# X-Fly.net
KiCad netlist of a schematic drawn in Altium Designer
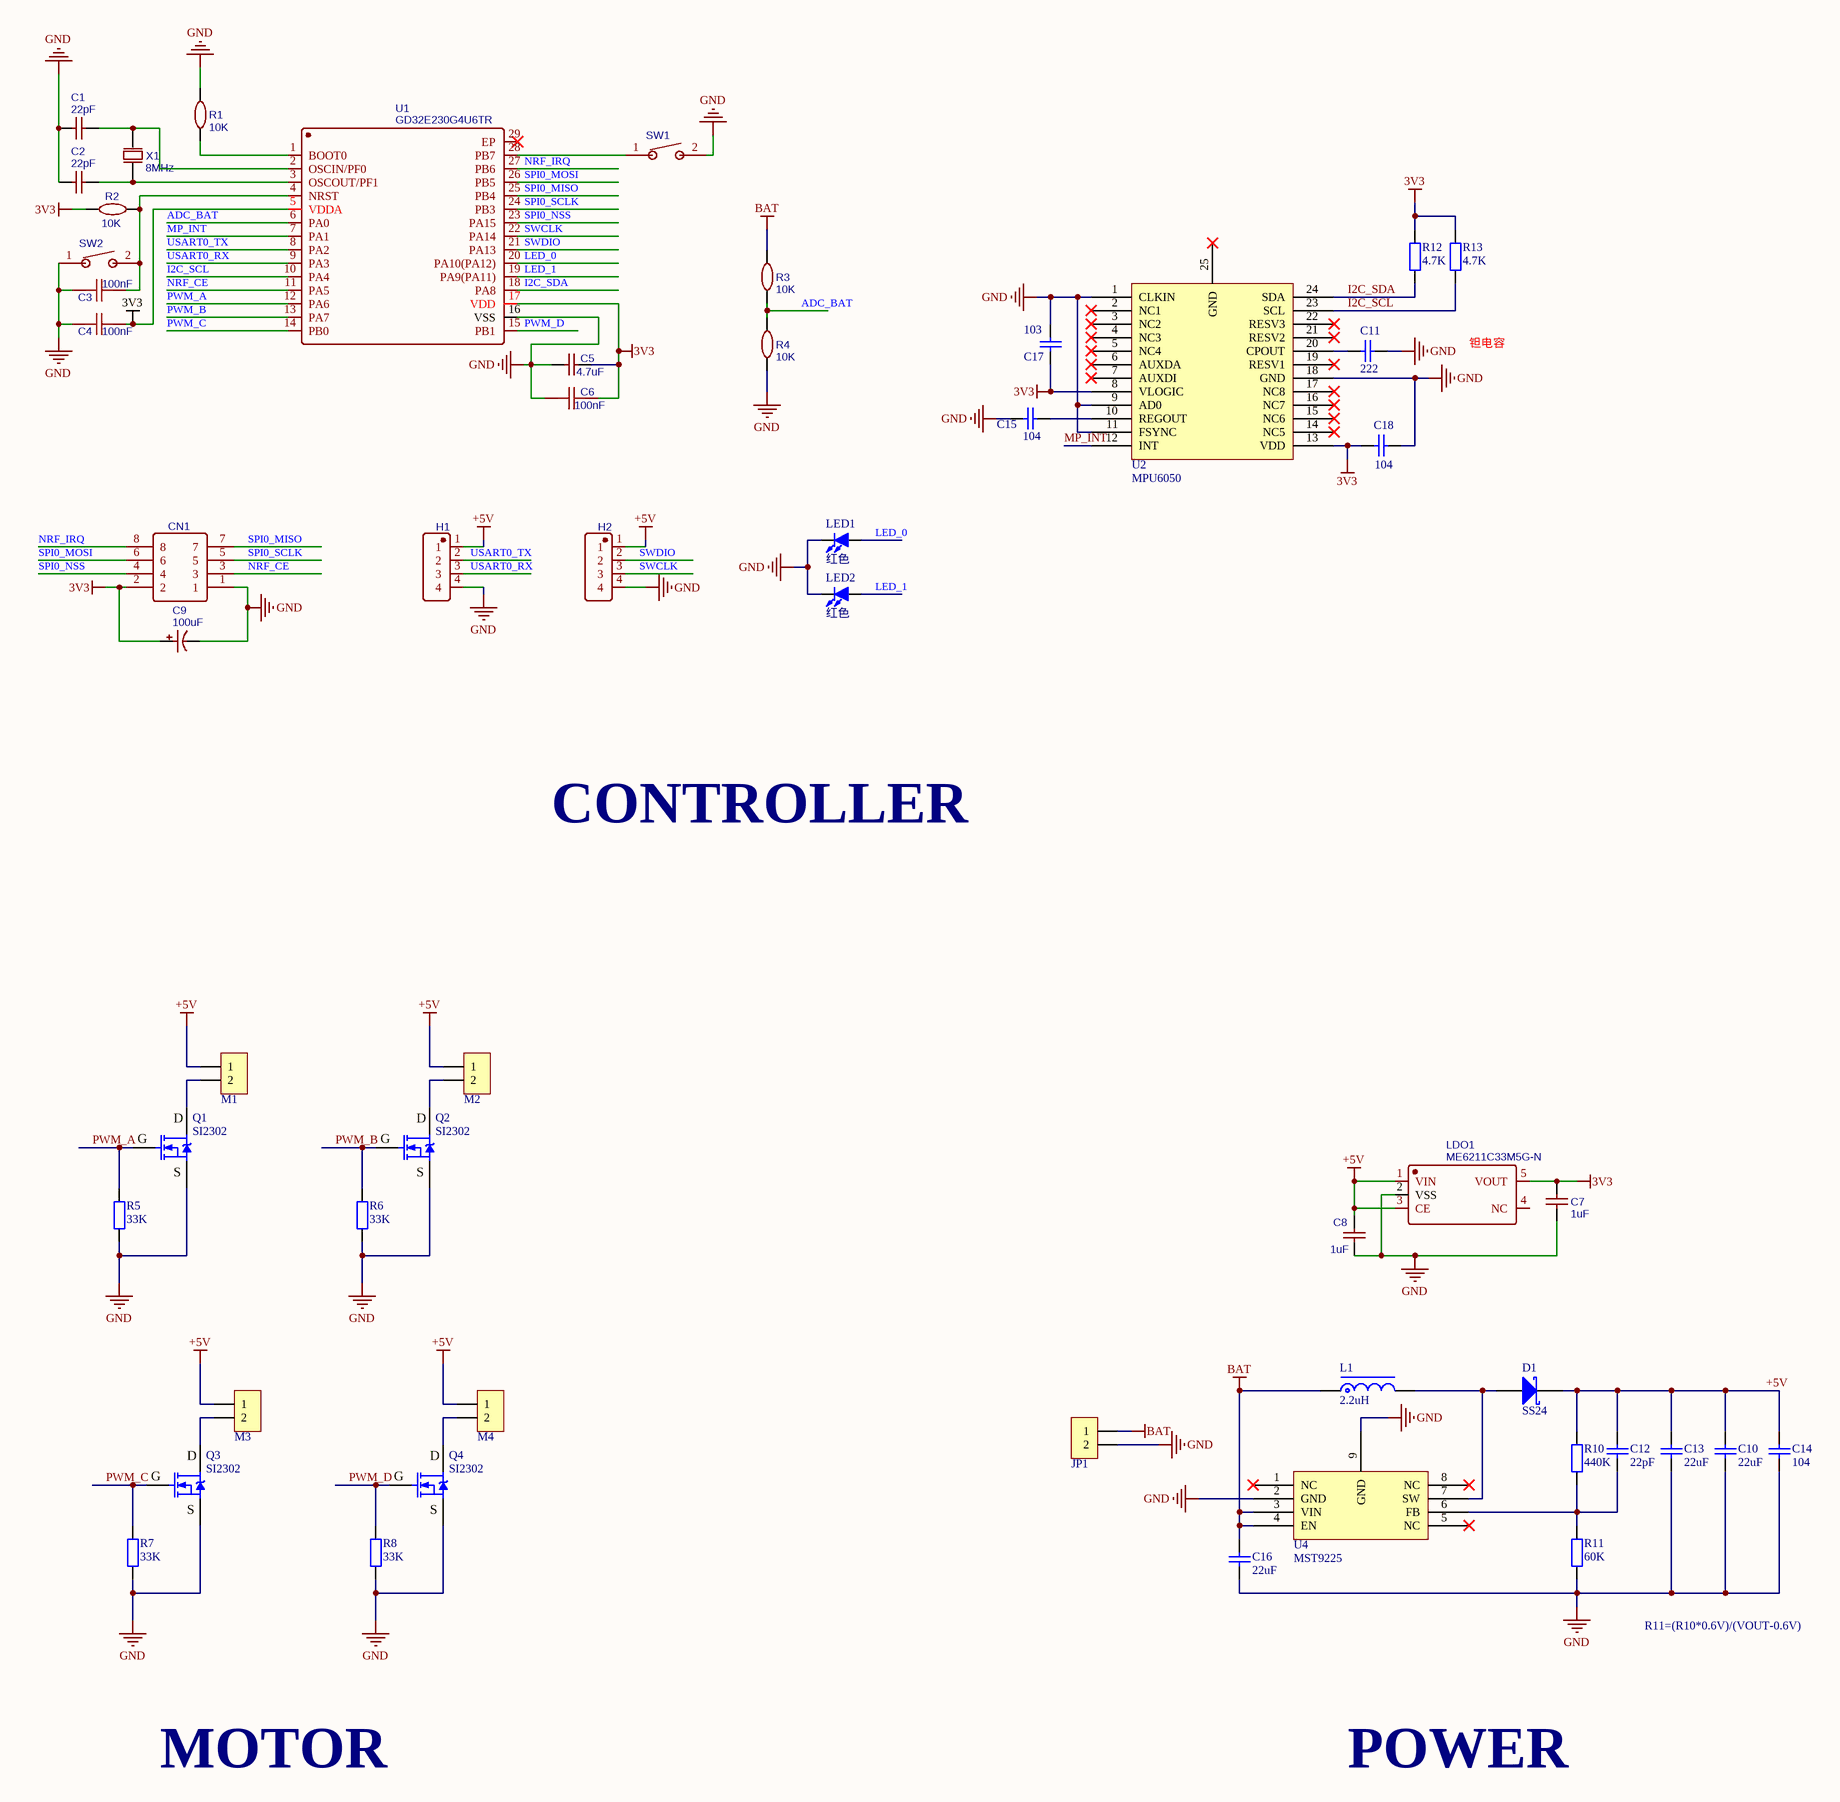
[diagram p0: X-Fly.SchDoc]

(export (version "E")
  (design (tool "Eeschema 10.0.6"))
  (components
    (comp (ref "C1")
      (value "22pF")
      (footprint "C0603_L")
      (fields
        (field (name "BOM_MANUFACTURER PART") "CC0603JRNPO9BN220")
        (field (name "BOM_SUPPLIER PART") "C105620")
      )
      (libsource (lib "altium-import") (part "root_0_22pF_"))
    )
    (comp (ref "C2")
      (value "22pF")
      (footprint "C0603_L")
      (fields
        (field (name "BOM_MANUFACTURER PART") "CC0603JRNPO9BN220")
        (field (name "BOM_SUPPLIER PART") "C105620")
      )
      (libsource (lib "altium-import") (part "root_0_22pF_"))
    )
    (comp (ref "C3")
      (value "100nF")
      (footprint "C0603_L")
      (fields
        (field (name "BOM_MANUFACTURER PART") "CC0603KRX7R9BB104")
        (field (name "BOM_SUPPLIER PART") "C14663")
      )
      (libsource (lib "altium-import") (part "root_2_100nF_"))
    )
    (comp (ref "C4")
      (value "100nF")
      (footprint "C0603_L")
      (fields
        (field (name "BOM_MANUFACTURER PART") "CC0603KRX7R9BB104")
        (field (name "BOM_SUPPLIER PART") "C14663")
      )
      (libsource (lib "altium-import") (part "root_0_100nF_"))
    )
    (comp (ref "C5")
      (value "4.7uF")
      (footprint "C0603_L")
      (fields
        (field (name "BOM_MANUFACTURER PART") "CL10A475KO8NNNC")
        (field (name "BOM_SUPPLIER PART") "C19666")
      )
      (libsource (lib "altium-import") (part "root_2_4.7uF_"))
    )
    (comp (ref "C6")
      (value "100nF")
      (footprint "C0603_L")
      (fields
        (field (name "BOM_MANUFACTURER PART") "CC0603KRX7R9BB104")
        (field (name "BOM_SUPPLIER PART") "C14663")
      )
      (libsource (lib "altium-import") (part "root_0_100nF_"))
    )
    (comp (ref "C7")
      (value "1uF")
      (footprint "C0603_L")
      (fields
        (field (name "BOM_MANUFACTURER PART") "CL10A105KB8NNNC")
        (field (name "BOM_SUPPLIER PART") "C15849")
      )
      (libsource (lib "altium-import") (part "root_1_1uF_"))
    )
    (comp (ref "C8")
      (value "1uF")
      (footprint "C0603_L")
      (fields
        (field (name "BOM_MANUFACTURER PART") "CL10A105KB8NNNC")
        (field (name "BOM_SUPPLIER PART") "C15849")
      )
      (libsource (lib "altium-import") (part "root_1_1uF_"))
    )
    (comp (ref "C9")
      (value "100uF")
      (footprint "CAP 2.5*6.3*11.2-H - BK")
      (fields
        (field (name "BOM_MANUFACTURER PART") "35YXJ100M6.3X11")
        (field (name "BOM_SUPPLIER PART") "C88754")
      )
      (libsource (lib "altium-import") (part "root_0_100uF_"))
    )
    (comp (ref "C10")
      (value "22uF")
      (footprint "C0603_L")
      (description "贴片电容")
      (libsource (lib "0.1 - 电阻-电容-电感-磁珠-电位器") (part "C"))
    )
    (comp (ref "C11")
      (value "222")
      (footprint "C_3216")
      (description "贴片电容")
      (libsource (lib "0.1 - 电阻-电容-电感-磁珠-电位器") (part "C"))
    )
    (comp (ref "C12")
      (value "22pF")
      (footprint "C0603_L")
      (description "贴片电容")
      (libsource (lib "0.1 - 电阻-电容-电感-磁珠-电位器") (part "C"))
    )
    (comp (ref "C13")
      (value "22uF")
      (footprint "C0603_L")
      (description "贴片电容")
      (libsource (lib "0.1 - 电阻-电容-电感-磁珠-电位器") (part "C"))
    )
    (comp (ref "C14")
      (value "104")
      (footprint "C0603_L")
      (description "贴片电容")
      (libsource (lib "0.1 - 电阻-电容-电感-磁珠-电位器") (part "C"))
    )
    (comp (ref "C15")
      (value "104")
      (footprint "C0603_L")
      (description "贴片电容")
      (libsource (lib "0.1 - 电阻-电容-电感-磁珠-电位器") (part "C"))
    )
    (comp (ref "C16")
      (value "22uF")
      (footprint "C0603_L")
      (description "贴片电容")
      (libsource (lib "0.1 - 电阻-电容-电感-磁珠-电位器") (part "C"))
    )
    (comp (ref "C17")
      (value "103")
      (footprint "C0603_L")
      (description "贴片电容")
      (libsource (lib "0.1 - 电阻-电容-电感-磁珠-电位器") (part "C"))
    )
    (comp (ref "C18")
      (value "104")
      (footprint "C0603_L")
      (description "贴片电容")
      (libsource (lib "0.1 - 电阻-电容-电感-磁珠-电位器") (part "C"))
    )
    (comp (ref "CN1")
      (value "A2005WV-2X4P")
      (footprint ".4G无线模块")
      (fields
        (field (name "BOM_SUPPLIER PART") "C225289")
        (field (name "BOM_MANUFACTURER PART") "A2005WV-2x4P")
        (field (name "CONTRIBUTOR") "LCSC")
      )
      (libsource (lib "altium-import") (part "root_1_A2005WV-2X4P_"))
    )
    (comp (ref "D1")
      (value "SS24")
      (footprint "SMB")
      (description "肖特基二极管")
      (libsource (lib "0.2 - 二极管-TVS-ESD-整流桥") (part "SS24"))
    )
    (comp (ref "H1")
      (value "1125-1104G0S116C001")
      (footprint "HDR2.54-WI-4P")
      (fields (field (name "BOM_SUPPLIER PART") "C920779") (field (name "CONTRIBUTOR") "LCSC"))
      (libsource (lib "altium-import") (part "root_0_1125-1104G0S116C001_"))
    )
    (comp (ref "H2")
      (value "1125-1104G0S116C001")
      (footprint "HDR2.54-WI-4P")
      (fields (field (name "BOM_SUPPLIER PART") "C920779") (field (name "CONTRIBUTOR") "LCSC"))
      (libsource (lib "altium-import") (part "root_0_1125-1104G0S116C001_"))
    )
    (comp (ref "JP1")
      (value "HDR-1X2")
      (footprint "XH2.54-WI-2P")
      (description "2P接插件")
      (libsource (lib "") (part "Header 2_1"))
    )
    (comp (ref "L1")
      (value "2.2uH")
      (footprint "CD52")
      (description "太诱-NR磁胶电感")
      (libsource (lib "0.1 - 电阻-电容-电感-磁珠-电位器") (part "L-NR"))
    )
    (comp (ref "LDO1")
      (value "ME6211C33M5G-N")
      (footprint "SOT-23-5")
      (fields (field (name "BOM_SUPPLIER PART") "C82942"))
      (libsource (lib "altium-import") (part "root_0_ME6211C33M5G-N_"))
    )
    (comp (ref "LED1")
      (value "红色")
      (footprint "LED0603_R")
      (description "贴片LED")
      (libsource (lib "0.3 - LED发光二极管") (part "LED-SMD"))
    )
    (comp (ref "LED2")
      (value "红色")
      (footprint "LED0603_R")
      (description "贴片LED")
      (libsource (lib "0.3 - LED发光二极管") (part "LED-SMD"))
    )
    (comp (ref "M1")
      (value "HDR-1X2")
      (footprint "XH2.54-WI-2P")
      (description "2P接插件")
      (libsource (lib "5.5 - 接插件-脚距2.54 (100mil) ") (part "Header 2"))
    )
    (comp (ref "M2")
      (value "HDR-1X2")
      (footprint "XH2.54-WI-2P")
      (description "2P接插件")
      (libsource (lib "5.5 - 接插件-脚距2.54 (100mil) ") (part "Header 2"))
    )
    (comp (ref "M3")
      (value "HDR-1X2")
      (footprint "XH2.54-WI-2P")
      (description "2P接插件")
      (libsource (lib "5.5 - 接插件-脚距2.54 (100mil) ") (part "Header 2"))
    )
    (comp (ref "M4")
      (value "HDR-1X2")
      (footprint "XH2.54-WI-2P")
      (description "2P接插件")
      (libsource (lib "5.5 - 接插件-脚距2.54 (100mil) ") (part "Header 2"))
    )
    (comp (ref "Q1")
      (value "SI2302")
      (footprint "SOT23-3N")
      (description "N沟道 20V/3A")
      (libsource (lib "0.4 - 三极管-场效应管-可控硅") (part "SI2302"))
    )
    (comp (ref "Q2")
      (value "SI2302")
      (footprint "SOT23-3N")
      (description "N沟道 20V/3A")
      (libsource (lib "0.4 - 三极管-场效应管-可控硅") (part "SI2302"))
    )
    (comp (ref "Q3")
      (value "SI2302")
      (footprint "SOT23-3N")
      (description "N沟道 20V/3A")
      (libsource (lib "0.4 - 三极管-场效应管-可控硅") (part "SI2302"))
    )
    (comp (ref "Q4")
      (value "SI2302")
      (footprint "SOT23-3N")
      (description "N沟道 20V/3A")
      (libsource (lib "0.4 - 三极管-场效应管-可控硅") (part "SI2302"))
    )
    (comp (ref "R1")
      (value "10K")
      (footprint "R0603_L")
      (fields
        (field (name "BOM_MANUFACTURER PART") "RC0603FR-0710KL")
        (field (name "BOM_SUPPLIER PART") "C98220")
      )
      (libsource (lib "altium-import") (part "root_1_10K_"))
    )
    (comp (ref "R2")
      (value "10K")
      (footprint "R0603_L")
      (fields
        (field (name "BOM_MANUFACTURER PART") "RC0603FR-0710KL")
        (field (name "BOM_SUPPLIER PART") "C98220")
      )
      (libsource (lib "altium-import") (part "root_2_10K_"))
    )
    (comp (ref "R3")
      (value "10K")
      (footprint "R0603_L")
      (fields
        (field (name "BOM_MANUFACTURER PART") "RC0603FR-0710KL")
        (field (name "BOM_SUPPLIER PART") "C98220")
      )
      (libsource (lib "altium-import") (part "root_3_10K_"))
    )
    (comp (ref "R4")
      (value "10K")
      (footprint "R0603_L")
      (fields
        (field (name "BOM_MANUFACTURER PART") "RC0603FR-0710KL")
        (field (name "BOM_SUPPLIER PART") "C98220")
      )
      (libsource (lib "altium-import") (part "root_3_10K_"))
    )
    (comp (ref "R5")
      (value "33K")
      (footprint "R0603_L")
      (description "贴片电阻")
      (libsource (lib "0.1 - 电阻-电容-电感-磁珠-电位器") (part "R"))
    )
    (comp (ref "R6")
      (value "33K")
      (footprint "R0603_L")
      (description "贴片电阻")
      (libsource (lib "0.1 - 电阻-电容-电感-磁珠-电位器") (part "R"))
    )
    (comp (ref "R7")
      (value "33K")
      (footprint "R0603_L")
      (description "贴片电阻")
      (libsource (lib "0.1 - 电阻-电容-电感-磁珠-电位器") (part "R"))
    )
    (comp (ref "R8")
      (value "33K")
      (footprint "R0603_L")
      (description "贴片电阻")
      (libsource (lib "0.1 - 电阻-电容-电感-磁珠-电位器") (part "R"))
    )
    (comp (ref "R10")
      (value "440K")
      (footprint "R0603_L")
      (description "贴片电阻")
      (libsource (lib "0.1 - 电阻-电容-电感-磁珠-电位器") (part "R"))
    )
    (comp (ref "R11")
      (value "60K")
      (footprint "R0603_L")
      (description "贴片电阻")
      (libsource (lib "0.1 - 电阻-电容-电感-磁珠-电位器") (part "R"))
    )
    (comp (ref "R12")
      (value "4.7K")
      (footprint "R0603_L")
      (description "贴片电阻")
      (libsource (lib "0.1 - 电阻-电容-电感-磁珠-电位器") (part "R"))
    )
    (comp (ref "R13")
      (value "4.7K")
      (footprint "R0603_L")
      (description "贴片电阻")
      (libsource (lib "0.1 - 电阻-电容-电感-磁珠-电位器") (part "R"))
    )
    (comp (ref "SW1")
      (value "TSA363G25-250B")
      (footprint "SW SMD-3*6*5")
      (fields (field (name "BOM_SUPPLIER PART") "C354943") (field (name "CONTRIBUTOR") "LCSC"))
      (libsource (lib "altium-import") (part "root_0_TSA363G25-250B_"))
    )
    (comp (ref "SW2")
      (value "TSA363G25-250B")
      (footprint "SW SMD-3*6*5")
      (fields (field (name "BOM_SUPPLIER PART") "C354943") (field (name "CONTRIBUTOR") "LCSC"))
      (libsource (lib "altium-import") (part "root_0_TSA363G25-250B_"))
    )
    (comp (ref "U1")
      (value "GD32E230G4U6TR")
      (footprint "QFN28 5x5_M")
      (fields (field (name "BOM_SUPPLIER PART") "C380784") (field (name "CONTRIBUTOR") "LCSC"))
      (libsource (lib "altium-import") (part "root_0_GD32E230G4U6TR_"))
    )
    (comp (ref "U2")
      (value "MPU6050")
      (footprint "QFN24 4x4_N")
      (libsource (lib "Aircraft Controller") (part "MPU6050"))
    )
    (comp (ref "U4")
      (value "MST9225")
      (footprint "ESOP8_N")
      (description "单节锂电池2A升压芯片")
      (libsource (lib "Aircraft Controller") (part "MST9225"))
    )
    (comp (ref "X1")
      (value "8MHz")
      (footprint "OSC 5032-2P")
      (fields (field (name "BOM_SUPPLIER PART") "C122522") (field (name "CONTRIBUTOR") "LCSC"))
      (libsource (lib "altium-import") (part "root_1_8MHz_"))
    )
  )
  (nets
    (net (code "1") (name "+5V") (class "Default")
      (node (ref "C10") (pin "2") (pinfunction "2_2") (pintype "passive"))
      (node (ref "C12") (pin "2") (pinfunction "2_2") (pintype "passive"))
      (node (ref "C13") (pin "2") (pinfunction "2_2") (pintype "passive"))
      (node (ref "C14") (pin "2") (pinfunction "2_2") (pintype "passive"))
      (node (ref "C8") (pin "2") (pinfunction "2_2") (pintype "passive"))
      (node (ref "D1") (pin "2") (pinfunction "K_2") (pintype "passive"))
      (node (ref "H1") (pin "1") (pinfunction "1_1") (pintype "passive"))
      (node (ref "H2") (pin "1") (pinfunction "1_1") (pintype "passive"))
      (node (ref "LDO1") (pin "1") (pinfunction "VIN_1") (pintype "passive"))
      (node (ref "LDO1") (pin "3") (pinfunction "CE_3") (pintype "passive"))
      (node (ref "M1") (pin "1") (pinfunction "1_1") (pintype "passive"))
      (node (ref "M2") (pin "1") (pinfunction "1_1") (pintype "passive"))
      (node (ref "M3") (pin "1") (pinfunction "1_1") (pintype "passive"))
      (node (ref "M4") (pin "1") (pinfunction "1_1") (pintype "passive"))
      (node (ref "R10") (pin "2") (pinfunction "2_2") (pintype "passive"))
    )
    (net (code "2") (name "/ADC_BAT") (class "Default")
      (node (ref "R3") (pin "2") (pinfunction "2_2") (pintype "passive"))
      (node (ref "R4") (pin "1") (pinfunction "1_1") (pintype "passive"))
      (node (ref "U1") (pin "6") (pinfunction "PA0_6") (pintype "passive"))
    )
    (net (code "3") (name "/I2C_SCL") (class "Default")
      (node (ref "R13") (pin "1") (pinfunction "1_1") (pintype "passive"))
      (node (ref "U1") (pin "10") (pinfunction "PA4_10") (pintype "passive"))
      (node (ref "U2") (pin "23") (pinfunction "SCL_23") (pintype "passive"))
    )
    (net (code "4") (name "/I2C_SDA") (class "Default")
      (node (ref "R12") (pin "1") (pinfunction "1_1") (pintype "passive"))
      (node (ref "U1") (pin "18") (pinfunction "PA8_18") (pintype "passive"))
      (node (ref "U2") (pin "24") (pinfunction "SDA_24") (pintype "passive"))
    )
    (net (code "5") (name "/LED_0") (class "Default")
      (node (ref "LED1") (pin "1") (pinfunction "A_1") (pintype "passive"))
      (node (ref "U1") (pin "20") (pinfunction "PA10(PA12)_20") (pintype "passive"))
    )
    (net (code "6") (name "/LED_1") (class "Default")
      (node (ref "LED2") (pin "1") (pinfunction "A_1") (pintype "passive"))
      (node (ref "U1") (pin "19") (pinfunction "PA9(PA11)_19") (pintype "passive"))
    )
    (net (code "7") (name "/MP_INT") (class "Default")
      (node (ref "U1") (pin "7") (pinfunction "PA1_7") (pintype "passive"))
      (node (ref "U2") (pin "12") (pinfunction "INT_12") (pintype "passive"))
    )
    (net (code "8") (name "/NRF_CE") (class "Default")
      (node (ref "CN1") (pin "3") (pinfunction "3_3") (pintype "passive"))
      (node (ref "U1") (pin "11") (pinfunction "PA5_11") (pintype "passive"))
    )
    (net (code "9") (name "/NRF_IRQ") (class "Default")
      (node (ref "CN1") (pin "8") (pinfunction "8_8") (pintype "passive"))
      (node (ref "U1") (pin "27") (pinfunction "PB6_27") (pintype "passive"))
    )
    (net (code "10") (name "/PWM_A") (class "Default")
      (node (ref "Q1") (pin "1") (pinfunction "G_1") (pintype "passive"))
      (node (ref "R5") (pin "2") (pinfunction "2_2") (pintype "passive"))
      (node (ref "U1") (pin "12") (pinfunction "PA6_12") (pintype "passive"))
    )
    (net (code "11") (name "/PWM_B") (class "Default")
      (node (ref "Q2") (pin "1") (pinfunction "G_1") (pintype "passive"))
      (node (ref "R6") (pin "2") (pinfunction "2_2") (pintype "passive"))
      (node (ref "U1") (pin "13") (pinfunction "PA7_13") (pintype "passive"))
    )
    (net (code "12") (name "/PWM_C") (class "Default")
      (node (ref "Q3") (pin "1") (pinfunction "G_1") (pintype "passive"))
      (node (ref "R7") (pin "2") (pinfunction "2_2") (pintype "passive"))
      (node (ref "U1") (pin "14") (pinfunction "PB0_14") (pintype "passive"))
    )
    (net (code "13") (name "/PWM_D") (class "Default")
      (node (ref "Q4") (pin "1") (pinfunction "G_1") (pintype "passive"))
      (node (ref "R8") (pin "2") (pinfunction "2_2") (pintype "passive"))
      (node (ref "U1") (pin "15") (pinfunction "PB1_15") (pintype "passive"))
    )
    (net (code "14") (name "/SPI0_MISO") (class "Default")
      (node (ref "CN1") (pin "7") (pinfunction "7_7") (pintype "passive"))
      (node (ref "U1") (pin "25") (pinfunction "PB4_25") (pintype "passive"))
    )
    (net (code "15") (name "/SPI0_MOSI") (class "Default")
      (node (ref "CN1") (pin "6") (pinfunction "6_6") (pintype "passive"))
      (node (ref "U1") (pin "26") (pinfunction "PB5_26") (pintype "passive"))
    )
    (net (code "16") (name "/SPI0_NSS") (class "Default")
      (node (ref "CN1") (pin "4") (pinfunction "4_4") (pintype "passive"))
      (node (ref "U1") (pin "23") (pinfunction "PA15_23") (pintype "passive"))
    )
    (net (code "17") (name "/SPI0_SCLK") (class "Default")
      (node (ref "CN1") (pin "5") (pinfunction "5_5") (pintype "passive"))
      (node (ref "U1") (pin "24") (pinfunction "PB3_24") (pintype "passive"))
    )
    (net (code "18") (name "/SWCLK") (class "Default")
      (node (ref "H2") (pin "3") (pinfunction "3_3") (pintype "passive"))
      (node (ref "U1") (pin "22") (pinfunction "PA14_22") (pintype "passive"))
    )
    (net (code "19") (name "/SWDIO") (class "Default")
      (node (ref "H2") (pin "2") (pinfunction "2_2") (pintype "passive"))
      (node (ref "U1") (pin "21") (pinfunction "PA13_21") (pintype "passive"))
    )
    (net (code "20") (name "/USART0_RX") (class "Default")
      (node (ref "H1") (pin "3") (pinfunction "3_3") (pintype "passive"))
      (node (ref "U1") (pin "9") (pinfunction "PA3_9") (pintype "passive"))
    )
    (net (code "21") (name "/USART0_TX") (class "Default")
      (node (ref "H1") (pin "2") (pinfunction "2_2") (pintype "passive"))
      (node (ref "U1") (pin "8") (pinfunction "PA2_8") (pintype "passive"))
    )
    (net (code "22") (name "3V3") (class "Default")
      (node (ref "C17") (pin "1") (pinfunction "1_1") (pintype "passive"))
      (node (ref "C18") (pin "1") (pinfunction "1_1") (pintype "passive"))
      (node (ref "C4") (pin "2") (pinfunction "2_2") (pintype "passive"))
      (node (ref "C5") (pin "1") (pinfunction "1_1") (pintype "passive"))
      (node (ref "C6") (pin "2") (pinfunction "2_2") (pintype "passive"))
      (node (ref "C7") (pin "2") (pinfunction "2_2") (pintype "passive"))
      (node (ref "C9") (pin "1") (pinfunction "1_1") (pintype "passive"))
      (node (ref "CN1") (pin "2") (pinfunction "2_2") (pintype "passive"))
      (node (ref "LDO1") (pin "5") (pinfunction "VOUT_5") (pintype "passive"))
      (node (ref "R12") (pin "2") (pinfunction "2_2") (pintype "passive"))
      (node (ref "R13") (pin "2") (pinfunction "2_2") (pintype "passive"))
      (node (ref "R2") (pin "2") (pinfunction "2_2") (pintype "passive"))
      (node (ref "U1") (pin "17") (pinfunction "VDD_17") (pintype "passive"))
      (node (ref "U1") (pin "5") (pinfunction "VDDA_5") (pintype "passive"))
      (node (ref "U2") (pin "13") (pinfunction "VDD_13") (pintype "passive"))
      (node (ref "U2") (pin "8") (pinfunction "VLOGIC_8") (pintype "passive"))
    )
    (net (code "23") (name "BAT") (class "Default")
      (node (ref "C16") (pin "2") (pinfunction "2_2") (pintype "passive"))
      (node (ref "JP1") (pin "1") (pinfunction "1_1") (pintype "passive"))
      (node (ref "L1") (pin "1") (pinfunction "1_1") (pintype "passive"))
      (node (ref "R3") (pin "1") (pinfunction "1_1") (pintype "passive"))
      (node (ref "U4") (pin "3") (pinfunction "VIN_3") (pintype "passive"))
      (node (ref "U4") (pin "4") (pinfunction "EN_4") (pintype "passive"))
    )
    (net (code "24") (name "GND") (class "Default")
      (node (ref "C1") (pin "1") (pinfunction "1_1") (pintype "passive"))
      (node (ref "C10") (pin "1") (pinfunction "1_1") (pintype "passive"))
      (node (ref "C11") (pin "1") (pinfunction "1_1") (pintype "passive"))
      (node (ref "C13") (pin "1") (pinfunction "1_1") (pintype "passive"))
      (node (ref "C14") (pin "1") (pinfunction "1_1") (pintype "passive"))
      (node (ref "C15") (pin "2") (pinfunction "2_2") (pintype "passive"))
      (node (ref "C16") (pin "1") (pinfunction "1_1") (pintype "passive"))
      (node (ref "C17") (pin "2") (pinfunction "2_2") (pintype "passive"))
      (node (ref "C18") (pin "2") (pinfunction "2_2") (pintype "passive"))
      (node (ref "C2") (pin "1") (pinfunction "1_1") (pintype "passive"))
      (node (ref "C3") (pin "2") (pinfunction "2_2") (pintype "passive"))
      (node (ref "C4") (pin "1") (pinfunction "1_1") (pintype "passive"))
      (node (ref "C5") (pin "2") (pinfunction "2_2") (pintype "passive"))
      (node (ref "C6") (pin "1") (pinfunction "1_1") (pintype "passive"))
      (node (ref "C7") (pin "1") (pinfunction "1_1") (pintype "passive"))
      (node (ref "C8") (pin "1") (pinfunction "1_1") (pintype "passive"))
      (node (ref "C9") (pin "2") (pinfunction "2_2") (pintype "passive"))
      (node (ref "CN1") (pin "1") (pinfunction "1_1") (pintype "passive"))
      (node (ref "H1") (pin "4") (pinfunction "4_4") (pintype "passive"))
      (node (ref "H2") (pin "4") (pinfunction "4_4") (pintype "passive"))
      (node (ref "JP1") (pin "2") (pinfunction "2_2") (pintype "passive"))
      (node (ref "LDO1") (pin "2") (pinfunction "VSS_2") (pintype "passive"))
      (node (ref "LED1") (pin "2") (pinfunction "K_2") (pintype "passive"))
      (node (ref "LED2") (pin "2") (pinfunction "K_2") (pintype "passive"))
      (node (ref "Q1") (pin "2") (pinfunction "S_2") (pintype "passive"))
      (node (ref "Q2") (pin "2") (pinfunction "S_2") (pintype "passive"))
      (node (ref "Q3") (pin "2") (pinfunction "S_2") (pintype "passive"))
      (node (ref "Q4") (pin "2") (pinfunction "S_2") (pintype "passive"))
      (node (ref "R1") (pin "2") (pinfunction "2_2") (pintype "passive"))
      (node (ref "R11") (pin "1") (pinfunction "1_1") (pintype "passive"))
      (node (ref "R4") (pin "2") (pinfunction "2_2") (pintype "passive"))
      (node (ref "R5") (pin "1") (pinfunction "1_1") (pintype "passive"))
      (node (ref "R6") (pin "1") (pinfunction "1_1") (pintype "passive"))
      (node (ref "R7") (pin "1") (pinfunction "1_1") (pintype "passive"))
      (node (ref "R8") (pin "1") (pinfunction "1_1") (pintype "passive"))
      (node (ref "SW1") (pin "2") (pinfunction "2_2") (pintype "passive"))
      (node (ref "SW2") (pin "1") (pinfunction "1_1") (pintype "passive"))
      (node (ref "U1") (pin "16") (pinfunction "VSS_16") (pintype "passive"))
      (node (ref "U2") (pin "1") (pinfunction "CLKIN_1") (pintype "passive"))
      (node (ref "U2") (pin "11") (pinfunction "FSYNC_11") (pintype "passive"))
      (node (ref "U2") (pin "18") (pinfunction "GND_18") (pintype "passive"))
      (node (ref "U2") (pin "9") (pinfunction "AD0_9") (pintype "passive"))
      (node (ref "U4") (pin "2") (pinfunction "GND_2") (pintype "passive"))
      (node (ref "U4") (pin "9") (pinfunction "GND_9") (pintype "passive"))
    )
    (net (code "25") (name "Net-(D1-A)") (class "Default")
      (node (ref "D1") (pin "1") (pinfunction "A_1") (pintype "passive"))
      (node (ref "L1") (pin "2") (pinfunction "2_2") (pintype "passive"))
      (node (ref "U4") (pin "7") (pinfunction "SW_7") (pintype "passive"))
    )
    (net (code "26") (name "Net-(Q1-D)") (class "Default")
      (node (ref "M1") (pin "2") (pinfunction "2_2") (pintype "passive"))
      (node (ref "Q1") (pin "3") (pinfunction "D_3") (pintype "passive"))
    )
    (net (code "27") (name "Net-(Q2-D)") (class "Default")
      (node (ref "M2") (pin "2") (pinfunction "2_2") (pintype "passive"))
      (node (ref "Q2") (pin "3") (pinfunction "D_3") (pintype "passive"))
    )
    (net (code "28") (name "Net-(Q3-D)") (class "Default")
      (node (ref "M3") (pin "2") (pinfunction "2_2") (pintype "passive"))
      (node (ref "Q3") (pin "3") (pinfunction "D_3") (pintype "passive"))
    )
    (net (code "29") (name "Net-(Q4-D)") (class "Default")
      (node (ref "M4") (pin "2") (pinfunction "2_2") (pintype "passive"))
      (node (ref "Q4") (pin "3") (pinfunction "D_3") (pintype "passive"))
    )
    (net (code "30") (name "Net-(U1-BOOT0)") (class "Default")
      (node (ref "R1") (pin "1") (pinfunction "1_1") (pintype "passive"))
      (node (ref "U1") (pin "1") (pinfunction "BOOT0_1") (pintype "passive"))
    )
    (net (code "31") (name "Net-(U1-NRST)") (class "Default")
      (node (ref "C3") (pin "1") (pinfunction "1_1") (pintype "passive"))
      (node (ref "R2") (pin "1") (pinfunction "1_1") (pintype "passive"))
      (node (ref "SW2") (pin "2") (pinfunction "2_2") (pintype "passive"))
      (node (ref "U1") (pin "4") (pinfunction "NRST_4") (pintype "passive"))
    )
    (net (code "32") (name "Net-(U1-OSCIN{slash}PF0)") (class "Default")
      (node (ref "C1") (pin "2") (pinfunction "2_2") (pintype "passive"))
      (node (ref "U1") (pin "2") (pinfunction "OSCIN/PF0_2") (pintype "passive"))
      (node (ref "X1") (pin "2") (pinfunction "OSC2_2") (pintype "passive"))
    )
    (net (code "33") (name "Net-(U1-OSCOUT{slash}PF1)") (class "Default")
      (node (ref "C2") (pin "2") (pinfunction "2_2") (pintype "passive"))
      (node (ref "U1") (pin "3") (pinfunction "OSCOUT/PF1_3") (pintype "passive"))
      (node (ref "X1") (pin "1") (pinfunction "OSC1_1") (pintype "passive"))
    )
    (net (code "34") (name "Net-(U1-PB7)") (class "Default")
      (node (ref "SW1") (pin "1") (pinfunction "1_1") (pintype "passive"))
      (node (ref "U1") (pin "28") (pinfunction "PB7_28") (pintype "passive"))
    )
    (net (code "35") (name "Net-(U2-CPOUT)") (class "Default")
      (node (ref "C11") (pin "2") (pinfunction "2_2") (pintype "passive"))
      (node (ref "U2") (pin "20") (pinfunction "CPOUT_20") (pintype "passive"))
    )
    (net (code "36") (name "Net-(U2-REGOUT)") (class "Default")
      (node (ref "C15") (pin "1") (pinfunction "1_1") (pintype "passive"))
      (node (ref "U2") (pin "10") (pinfunction "REGOUT_10") (pintype "passive"))
    )
    (net (code "37") (name "Net-(U4-FB)") (class "Default")
      (node (ref "C12") (pin "1") (pinfunction "1_1") (pintype "passive"))
      (node (ref "R10") (pin "1") (pinfunction "1_1") (pintype "passive"))
      (node (ref "R11") (pin "2") (pinfunction "2_2") (pintype "passive"))
      (node (ref "U4") (pin "6") (pinfunction "FB_6") (pintype "passive"))
    )
    (net (code "38") (name "unconnected-(LDO1-NC-Pad4)") (class "Default")
      (node (ref "LDO1") (pin "4") (pinfunction "NC_4") (pintype "passive"))
    )
    (net (code "39") (name "unconnected-(U1-EP-Pad29)") (class "Default")
      (node (ref "U1") (pin "29") (pinfunction "EP_29") (pintype "passive+no_connect"))
    )
    (net (code "40") (name "unconnected-(U2-AUXDA-Pad6)") (class "Default")
      (node (ref "U2") (pin "6") (pinfunction "AUXDA_6") (pintype "passive+no_connect"))
    )
    (net (code "41") (name "unconnected-(U2-AUXDI-Pad7)") (class "Default")
      (node (ref "U2") (pin "7") (pinfunction "AUXDI_7") (pintype "passive+no_connect"))
    )
    (net (code "42") (name "unconnected-(U2-GND-Pad25)") (class "Default")
      (node (ref "U2") (pin "25") (pinfunction "GND_25") (pintype "passive+no_connect"))
    )
    (net (code "43") (name "unconnected-(U2-NC1-Pad2)") (class "Default")
      (node (ref "U2") (pin "2") (pinfunction "NC1_2") (pintype "passive+no_connect"))
    )
    (net (code "44") (name "unconnected-(U2-NC2-Pad3)") (class "Default")
      (node (ref "U2") (pin "3") (pinfunction "NC2_3") (pintype "passive+no_connect"))
    )
    (net (code "45") (name "unconnected-(U2-NC3-Pad4)") (class "Default")
      (node (ref "U2") (pin "4") (pinfunction "NC3_4") (pintype "passive+no_connect"))
    )
    (net (code "46") (name "unconnected-(U2-NC4-Pad5)") (class "Default")
      (node (ref "U2") (pin "5") (pinfunction "NC4_5") (pintype "passive+no_connect"))
    )
    (net (code "47") (name "unconnected-(U2-NC5-Pad14)") (class "Default")
      (node (ref "U2") (pin "14") (pinfunction "NC5_14") (pintype "passive+no_connect"))
    )
    (net (code "48") (name "unconnected-(U2-NC6-Pad15)") (class "Default")
      (node (ref "U2") (pin "15") (pinfunction "NC6_15") (pintype "passive+no_connect"))
    )
    (net (code "49") (name "unconnected-(U2-NC7-Pad16)") (class "Default")
      (node (ref "U2") (pin "16") (pinfunction "NC7_16") (pintype "passive+no_connect"))
    )
    (net (code "50") (name "unconnected-(U2-NC8-Pad17)") (class "Default")
      (node (ref "U2") (pin "17") (pinfunction "NC8_17") (pintype "passive+no_connect"))
    )
    (net (code "51") (name "unconnected-(U2-RESV1-Pad19)") (class "Default")
      (node (ref "U2") (pin "19") (pinfunction "RESV1_19") (pintype "passive+no_connect"))
    )
    (net (code "52") (name "unconnected-(U2-RESV2-Pad21)") (class "Default")
      (node (ref "U2") (pin "21") (pinfunction "RESV2_21") (pintype "passive+no_connect"))
    )
    (net (code "53") (name "unconnected-(U2-RESV3-Pad22)") (class "Default")
      (node (ref "U2") (pin "22") (pinfunction "RESV3_22") (pintype "passive+no_connect"))
    )
    (net (code "54") (name "unconnected-(U4-NC-Pad1)") (class "Default")
      (node (ref "U4") (pin "1") (pinfunction "NC_1") (pintype "passive+no_connect"))
    )
    (net (code "55") (name "unconnected-(U4-NC-Pad5)") (class "Default")
      (node (ref "U4") (pin "5") (pinfunction "NC_5") (pintype "passive+no_connect"))
    )
    (net (code "56") (name "unconnected-(U4-NC-Pad8)") (class "Default")
      (node (ref "U4") (pin "8") (pinfunction "NC_8") (pintype "passive+no_connect"))
    )
  )
)
